# 800U-R3N3_IB_LED_V1_0.net
KiCad netlist of a schematic drawn in Altium Designer
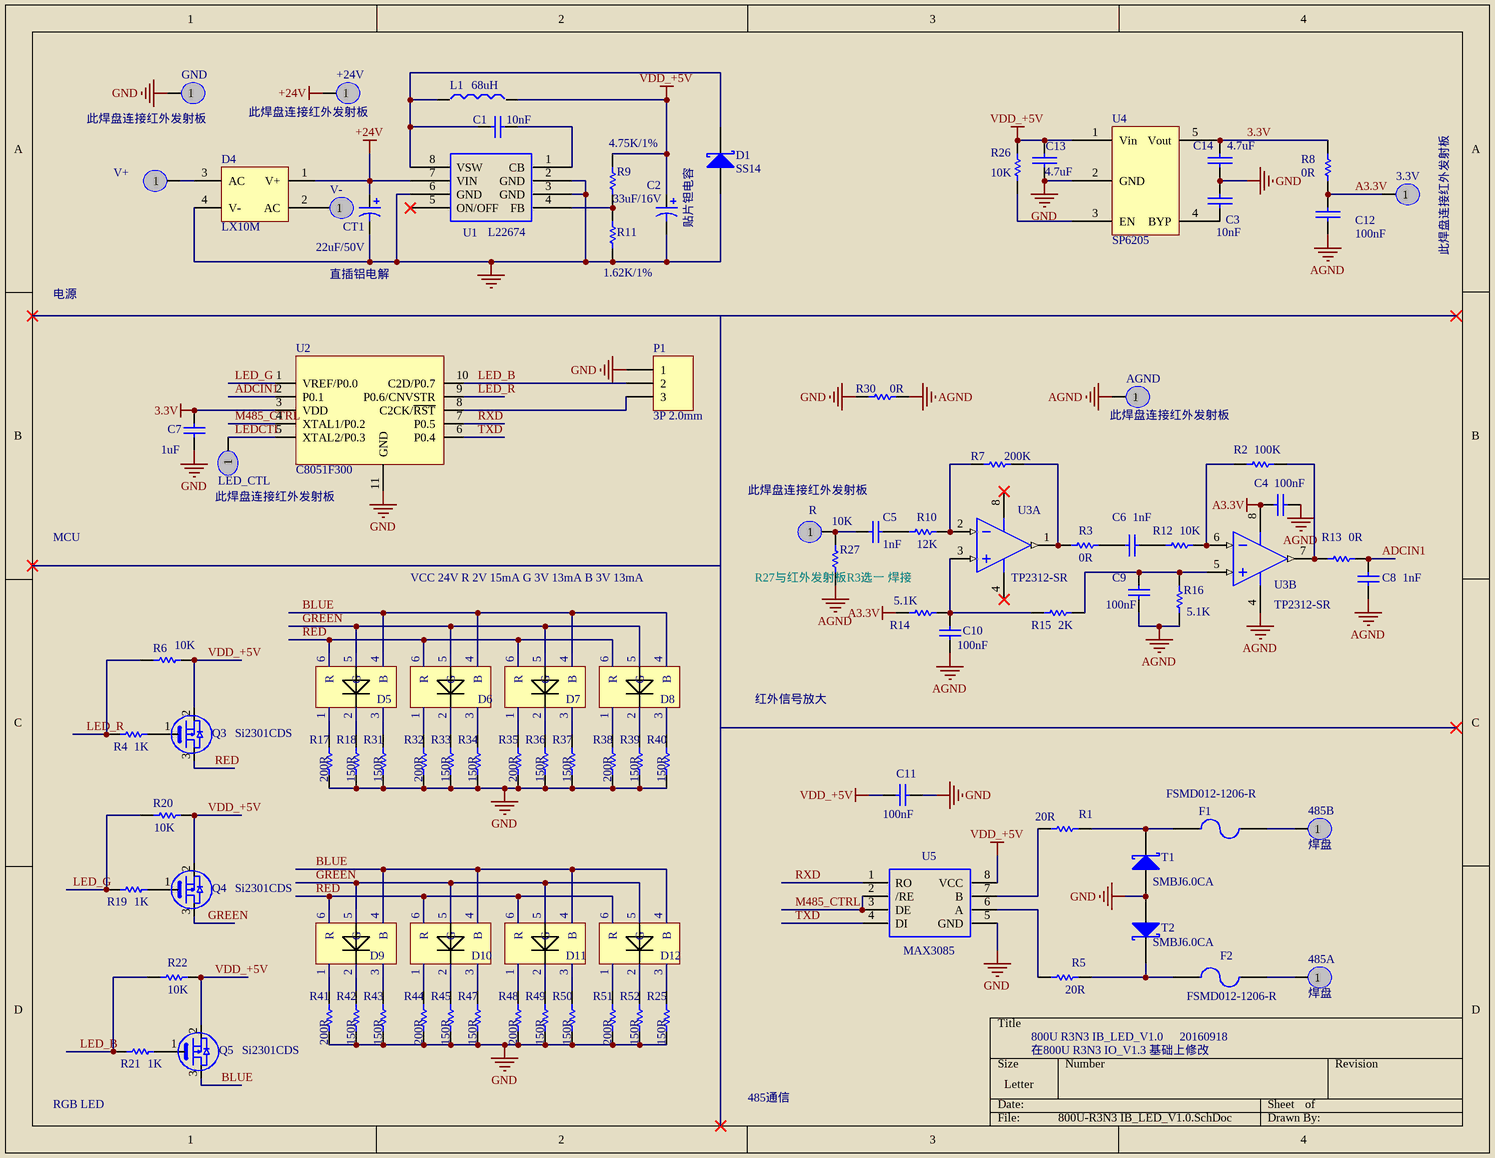
[diagram p0: 800U-R3N3 IB_LED_V1.0.SchDoc]

(export (version "E")
  (design (tool "Eeschema 10.0.6"))
  (components
    (comp (ref "+24V")
      (value "~")
      (footprint "HOLE_SMD")
      (fields (field (name "ALTIUM_UNNAMED_1") "此焊盘连接红外发射板"))
      (libsource (lib "MODBUS_V1.0") (part "焊盘"))
    )
    (comp (ref "3.3V")
      (value "~")
      (footprint "HOLE_SMD")
      (fields (field (name "ALTIUM_UNNAMED_1") "此焊盘连接红外发射板"))
      (libsource (lib "MODBUS_V1.0") (part "焊盘"))
    )
    (comp (ref "485A") (value "焊盘") (footprint "HOLE_SMD") (libsource (lib "MODBUS_V1.0") (part "焊盘")))
    (comp (ref "485B") (value "焊盘") (footprint "HOLE_SMD") (libsource (lib "MODBUS_V1.0") (part "焊盘")))
    (comp (ref "AGND")
      (value "~")
      (footprint "HOLE_SMD")
      (fields (field (name "ALTIUM_UNNAMED_1") "此焊盘连接红外发射板"))
      (libsource (lib "MODBUS_V1.0") (part "焊盘"))
    )
    (comp (ref "C1")
      (value "10nF")
      (footprint "C0603")
      (description "Capacitor")
      (fields (field (name "PUBLISHER") "Altium Limited"))
      (libsource (lib "*") (part "Cap"))
    )
    (comp (ref "C2")
      (value "33uF/16V")
      (footprint "CT3528")
      (description "Polarized Capacitor (Radial)")
      (fields (field (name "KIND") "贴片钽电容"))
      (libsource (lib "*") (part "Cap Pol1"))
    )
    (comp (ref "C3")
      (value "10nF")
      (footprint "C0603")
      (description "Capacitor")
      (libsource (lib "*") (part "CAP"))
    )
    (comp (ref "C4")
      (value "100nF")
      (footprint "C0603")
      (description "Capacitor")
      (fields (field (name "PUBLISHER") "Altium Limited"))
      (libsource (lib "TMJD1.0") (part "Cap"))
    )
    (comp (ref "C5")
      (value "1nF")
      (footprint "C0603")
      (description "Capacitor")
      (fields (field (name "PUBLISHER") "Altium Limited"))
      (libsource (lib "TMJD1.0") (part "Cap"))
    )
    (comp (ref "C6")
      (value "1nF")
      (footprint "C0603")
      (description "Capacitor")
      (fields (field (name "PUBLISHER") "Altium Limited"))
      (libsource (lib "TMJD1.0") (part "Cap"))
    )
    (comp (ref "C7")
      (value "1uF")
      (footprint "C0603")
      (description "贴片电容")
      (fields (field (name "PUBLISHER") "Altium Limited"))
      (libsource (lib "TMJD1.0") (part "Cap"))
    )
    (comp (ref "C8")
      (value "1nF")
      (footprint "C0603")
      (description "Capacitor")
      (fields (field (name "PUBLISHER") "Altium Limited"))
      (libsource (lib "TMJD1.0") (part "Cap"))
    )
    (comp (ref "C9")
      (value "100nF")
      (footprint "C0603")
      (description "Capacitor")
      (fields (field (name "PUBLISHER") "Altium Limited"))
      (libsource (lib "TMJD1.0") (part "Cap"))
    )
    (comp (ref "C10")
      (value "100nF")
      (footprint "C0603")
      (description "Capacitor")
      (fields (field (name "PUBLISHER") "Altium Limited"))
      (libsource (lib "TMJD1.0") (part "Cap"))
    )
    (comp (ref "C11")
      (value "100nF")
      (footprint "C0603")
      (description "贴片陶瓷电容")
      (libsource (lib "Miscellaneous Devices") (part "Cap"))
    )
    (comp (ref "C12")
      (value "100nF")
      (footprint "C0603")
      (description "Capacitor")
      (libsource (lib "*") (part "CAP"))
    )
    (comp (ref "C13")
      (value "4.7uF")
      (footprint "C0603")
      (description "Capacitor")
      (libsource (lib "*") (part "CAP"))
    )
    (comp (ref "C14")
      (value "4.7uF")
      (footprint "C0603")
      (description "Capacitor")
      (libsource (lib "*") (part "CAP"))
    )
    (comp (ref "CT1")
      (value "22uF/50V")
      (footprint "RB0.1")
      (description "Polarized Capacitor (Radial)")
      (fields (field (name "KIND") "直插铝电解"))
      (libsource (lib "*") (part "Cap Pol1"))
    )
    (comp (ref "D1") (value "SS14") (footprint "SMB") (libsource (lib "*") (part "SMBJ6.0CA")))
    (comp (ref "D4")
      (value "LX10M")
      (footprint "桥堆 3.8*3.5")
      (description "贴片桥堆")
      (libsource (lib "Miscellaneous Devices") (part "Bridge2"))
    )
    (comp (ref "D5")
      (value "5050RGB")
      (footprint "5050RGB")
      (description "RBG发光管")
      (libsource (lib "MODBUS_V1.0") (part "5050RGB"))
    )
    (comp (ref "D6")
      (value "5050RGB")
      (footprint "5050RGB")
      (description "RBG发光管")
      (libsource (lib "MODBUS_V1.0") (part "5050RGB"))
    )
    (comp (ref "D7")
      (value "5050RGB")
      (footprint "5050RGB")
      (description "RBG发光管")
      (libsource (lib "MODBUS_V1.0") (part "5050RGB"))
    )
    (comp (ref "D8")
      (value "5050RGB")
      (footprint "5050RGB")
      (description "RBG发光管")
      (libsource (lib "MODBUS_V1.0") (part "5050RGB"))
    )
    (comp (ref "D9")
      (value "5050RGB")
      (footprint "5050RGB")
      (description "RBG发光管")
      (libsource (lib "MODBUS_V1.0") (part "5050RGB"))
    )
    (comp (ref "D10")
      (value "5050RGB")
      (footprint "5050RGB")
      (description "RBG发光管")
      (libsource (lib "MODBUS_V1.0") (part "5050RGB"))
    )
    (comp (ref "D11")
      (value "5050RGB")
      (footprint "5050RGB")
      (description "RBG发光管")
      (libsource (lib "MODBUS_V1.0") (part "5050RGB"))
    )
    (comp (ref "D12")
      (value "5050RGB")
      (footprint "5050RGB")
      (description "RBG发光管")
      (libsource (lib "MODBUS_V1.0") (part "5050RGB"))
    )
    (comp (ref "F1")
      (value "FSMD012-1206-R")
      (footprint "1206")
      (description "可恢复保险丝")
      (libsource (lib "Miscellaneous Devices") (part "Fuse 2"))
    )
    (comp (ref "F2")
      (value "FSMD012-1206-R")
      (footprint "1206")
      (description "可恢复保险丝")
      (libsource (lib "Miscellaneous Devices") (part "Fuse 2"))
    )
    (comp (ref "GND")
      (value "~")
      (footprint "HOLE_SMD")
      (fields (field (name "ALTIUM_UNNAMED_1") "此焊盘连接红外发射板"))
      (libsource (lib "MODBUS_V1.0") (part "焊盘"))
    )
    (comp (ref "L1") (value "68uH") (footprint "L-6X6") (libsource (lib "*") (part "电感")))
    (comp (ref "LED_CTL")
      (value "~")
      (footprint "HOLE_SMD")
      (fields (field (name "ALTIUM_UNNAMED_1") "此焊盘连接红外发射板"))
      (libsource (lib "MODBUS_V1.0") (part "焊盘"))
    )
    (comp (ref "P1")
      (value "3P 2.0mm")
      (footprint "SIP3")
      (description "插座")
      (fields (field (name "PUBLISHER") "Altium Limited"))
      (libsource (lib "Miscellaneous Connectors") (part "MHDR1X3"))
    )
    (comp (ref "Q3")
      (value "Si2301CDS")
      (footprint "SOT-23")
      (description "贴片MOS管")
      (libsource (lib "BATTERY") (part "P-MOSFET"))
    )
    (comp (ref "Q4")
      (value "Si2301CDS")
      (footprint "SOT-23")
      (description "贴片MOS管")
      (libsource (lib "BATTERY") (part "P-MOSFET"))
    )
    (comp (ref "Q5")
      (value "Si2301CDS")
      (footprint "SOT-23")
      (description "贴片MOS管")
      (libsource (lib "BATTERY") (part "P-MOSFET"))
    )
    (comp (ref "R")
      (value "~")
      (footprint "HOLE_SMD")
      (fields (field (name "ALTIUM_UNNAMED_1") "此焊盘连接红外发射板"))
      (libsource (lib "MODBUS_V1.0") (part "焊盘"))
    )
    (comp (ref "R1")
      (value "20R")
      (footprint "2010")
      (description "贴片电阻")
      (libsource (lib "Miscellaneous Devices") (part "Res Semi"))
    )
    (comp (ref "R2")
      (value "100K")
      (footprint "R0603")
      (description "Semiconductor Resistor")
      (libsource (lib "Miscellaneous Devices") (part "Res Semi"))
    )
    (comp (ref "R3")
      (value "0R")
      (footprint "R0603")
      (description "Semiconductor Resistor")
      (libsource (lib "Miscellaneous Devices") (part "Res Semi"))
    )
    (comp (ref "R4")
      (value "1K")
      (footprint "R0603")
      (description "贴片电阻")
      (libsource (lib "Miscellaneous Devices") (part "Res Semi"))
    )
    (comp (ref "R5")
      (value "20R")
      (footprint "2010")
      (description "贴片电阻")
      (libsource (lib "Miscellaneous Devices") (part "Res Semi"))
    )
    (comp (ref "R6")
      (value "10K")
      (footprint "R0603")
      (description "贴片电阻")
      (libsource (lib "Miscellaneous Devices") (part "Res Semi"))
    )
    (comp (ref "R7")
      (value "200K")
      (footprint "R0603")
      (description "Semiconductor Resistor")
      (libsource (lib "Miscellaneous Devices") (part "Res Semi"))
    )
    (comp (ref "R8")
      (value "0R")
      (footprint "R0603")
      (description "Resistor")
      (fields (field (name "PUBLISHER") "Altium Limited"))
      (libsource (lib "*") (part "Res1"))
    )
    (comp (ref "R9")
      (value "4.75K/1%")
      (footprint "R0603")
      (description "Semiconductor Resistor")
      (fields (field (name "PUBLISHER") "Altium Limited"))
      (libsource (lib "*") (part "Res Semi"))
    )
    (comp (ref "R10")
      (value "12K")
      (footprint "R0603")
      (description "Semiconductor Resistor")
      (libsource (lib "Miscellaneous Devices") (part "Res Semi"))
    )
    (comp (ref "R11")
      (value "1.62K/1%")
      (footprint "R0603")
      (description "Semiconductor Resistor")
      (fields (field (name "PUBLISHER") "Altium Limited"))
      (libsource (lib "*") (part "Res Semi"))
    )
    (comp (ref "R12")
      (value "10K")
      (footprint "R0603")
      (description "Semiconductor Resistor")
      (libsource (lib "Miscellaneous Devices") (part "Res Semi"))
    )
    (comp (ref "R13")
      (value "0R")
      (footprint "R0603")
      (description "Semiconductor Resistor")
      (libsource (lib "Miscellaneous Devices") (part "Res Semi"))
    )
    (comp (ref "R14")
      (value "5.1K")
      (footprint "R0603")
      (description "Semiconductor Resistor")
      (libsource (lib "Miscellaneous Devices") (part "Res Semi"))
    )
    (comp (ref "R15")
      (value "2K")
      (footprint "R0603")
      (description "Semiconductor Resistor")
      (libsource (lib "Miscellaneous Devices") (part "Res Semi"))
    )
    (comp (ref "R16")
      (value "5.1K")
      (footprint "R0603")
      (description "Semiconductor Resistor")
      (libsource (lib "Miscellaneous Devices") (part "Res Semi"))
    )
    (comp (ref "R17")
      (value "200R")
      (footprint "0805")
      (description "贴片电阻")
      (libsource (lib "Miscellaneous Devices") (part "Res Semi"))
    )
    (comp (ref "R18")
      (value "150R")
      (footprint "0805")
      (description "贴片电阻")
      (libsource (lib "Miscellaneous Devices") (part "Res Semi"))
    )
    (comp (ref "R19")
      (value "1K")
      (footprint "R0603")
      (description "贴片电阻")
      (libsource (lib "Miscellaneous Devices") (part "Res Semi"))
    )
    (comp (ref "R20")
      (value "10K")
      (footprint "R0603")
      (description "贴片电阻")
      (libsource (lib "Miscellaneous Devices") (part "Res Semi"))
    )
    (comp (ref "R21")
      (value "1K")
      (footprint "R0603")
      (description "贴片电阻")
      (libsource (lib "Miscellaneous Devices") (part "Res Semi"))
    )
    (comp (ref "R22")
      (value "10K")
      (footprint "R0603")
      (description "贴片电阻")
      (libsource (lib "Miscellaneous Devices") (part "Res Semi"))
    )
    (comp (ref "R25")
      (value "150R")
      (footprint "0805")
      (description "贴片电阻")
      (libsource (lib "Miscellaneous Devices") (part "Res Semi"))
    )
    (comp (ref "R26")
      (value "10K")
      (footprint "R0603")
      (description "Resistor")
      (fields (field (name "PUBLISHER") "Altium Limited"))
      (libsource (lib "*") (part "Res1"))
    )
    (comp (ref "R27")
      (value "10K")
      (footprint "R0603")
      (description "Semiconductor Resistor")
      (fields (field (name "ALTIUM_UNNAMED_1") "R27与红外发射板R3选一 焊接"))
      (libsource (lib "Miscellaneous Devices") (part "Res Semi"))
    )
    (comp (ref "R30")
      (value "0R")
      (footprint "R0603")
      (description "Semiconductor Resistor")
      (libsource (lib "Miscellaneous Devices") (part "Res Semi"))
    )
    (comp (ref "R31")
      (value "150R")
      (footprint "0805")
      (description "贴片电阻")
      (libsource (lib "Miscellaneous Devices") (part "Res Semi"))
    )
    (comp (ref "R32")
      (value "200R")
      (footprint "0805")
      (description "贴片电阻")
      (libsource (lib "Miscellaneous Devices") (part "Res Semi"))
    )
    (comp (ref "R33")
      (value "150R")
      (footprint "0805")
      (description "贴片电阻")
      (libsource (lib "Miscellaneous Devices") (part "Res Semi"))
    )
    (comp (ref "R34")
      (value "150R")
      (footprint "0805")
      (description "贴片电阻")
      (libsource (lib "Miscellaneous Devices") (part "Res Semi"))
    )
    (comp (ref "R35")
      (value "200R")
      (footprint "0805")
      (description "贴片电阻")
      (libsource (lib "Miscellaneous Devices") (part "Res Semi"))
    )
    (comp (ref "R36")
      (value "150R")
      (footprint "0805")
      (description "贴片电阻")
      (libsource (lib "Miscellaneous Devices") (part "Res Semi"))
    )
    (comp (ref "R37")
      (value "150R")
      (footprint "0805")
      (description "贴片电阻")
      (libsource (lib "Miscellaneous Devices") (part "Res Semi"))
    )
    (comp (ref "R38")
      (value "200R")
      (footprint "0805")
      (description "贴片电阻")
      (libsource (lib "Miscellaneous Devices") (part "Res Semi"))
    )
    (comp (ref "R39")
      (value "150R")
      (footprint "0805")
      (description "贴片电阻")
      (libsource (lib "Miscellaneous Devices") (part "Res Semi"))
    )
    (comp (ref "R40")
      (value "150R")
      (footprint "0805")
      (description "贴片电阻")
      (libsource (lib "Miscellaneous Devices") (part "Res Semi"))
    )
    (comp (ref "R41")
      (value "200R")
      (footprint "0805")
      (description "贴片电阻")
      (libsource (lib "Miscellaneous Devices") (part "Res Semi"))
    )
    (comp (ref "R42")
      (value "150R")
      (footprint "0805")
      (description "贴片电阻")
      (libsource (lib "Miscellaneous Devices") (part "Res Semi"))
    )
    (comp (ref "R43")
      (value "150R")
      (footprint "0805")
      (description "贴片电阻")
      (libsource (lib "Miscellaneous Devices") (part "Res Semi"))
    )
    (comp (ref "R44")
      (value "200R")
      (footprint "0805")
      (description "贴片电阻")
      (libsource (lib "Miscellaneous Devices") (part "Res Semi"))
    )
    (comp (ref "R45")
      (value "150R")
      (footprint "0805")
      (description "贴片电阻")
      (libsource (lib "Miscellaneous Devices") (part "Res Semi"))
    )
    (comp (ref "R47")
      (value "150R")
      (footprint "0805")
      (description "贴片电阻")
      (libsource (lib "Miscellaneous Devices") (part "Res Semi"))
    )
    (comp (ref "R48")
      (value "200R")
      (footprint "0805")
      (description "贴片电阻")
      (libsource (lib "Miscellaneous Devices") (part "Res Semi"))
    )
    (comp (ref "R49")
      (value "150R")
      (footprint "0805")
      (description "贴片电阻")
      (libsource (lib "Miscellaneous Devices") (part "Res Semi"))
    )
    (comp (ref "R50")
      (value "150R")
      (footprint "0805")
      (description "贴片电阻")
      (libsource (lib "Miscellaneous Devices") (part "Res Semi"))
    )
    (comp (ref "R51")
      (value "200R")
      (footprint "0805")
      (description "贴片电阻")
      (libsource (lib "Miscellaneous Devices") (part "Res Semi"))
    )
    (comp (ref "R52")
      (value "150R")
      (footprint "0805")
      (description "贴片电阻")
      (libsource (lib "Miscellaneous Devices") (part "Res Semi"))
    )
    (comp (ref "T1")
      (value "~")
      (footprint "HSMA")
      (description "TVS管")
      (fields (field (name "型号") "SMBJ6.0CA"))
      (libsource (lib "MODBUS_V1.0") (part "SMBJ6.0CA"))
    )
    (comp (ref "T2")
      (value "~")
      (footprint "HSMA")
      (description "TVS管")
      (fields (field (name "型号") "SMBJ6.0CA"))
      (libsource (lib "MODBUS_V1.0") (part "SMBJ6.0CA"))
    )
    (comp (ref "U1") (value "L22674") (footprint "SO-1.27-9/4.0") (libsource (lib "*") (part "2674")))
    (comp (ref "U2")
      (value "C8051F300")
      (footprint "QFN-11")
      (description "贴片芯片")
      (libsource (lib "集成块") (part "PIC16C505"))
    )
    (comp (ref "U3")
      (value "TP2312-SR")
      (footprint "SO-8")
      (description "Dual Low Noise, Audio Amplifier")
      (fields (field (name "PUBLISHER") "Altium Limited"))
      (libsource (lib "Motorola Amplifier Audio Amplifier") (part "LM833D"))
    )
    (comp (ref "U4")
      (value "SP6205")
      (footprint "SOT-23-5")
      (libsource (lib "MODBUS_V1.0") (part "SP6203/SP6205"))
    )
    (comp (ref "U5")
      (value "MAX3085")
      (footprint "SO-1.27-8/4.0")
      (description "贴片芯片")
      (libsource (lib "*") (part "MAX_485"))
    )
    (comp (ref "V+") (value "~") (footprint "HOLE_SMD") (libsource (lib "MODBUS_V1.0") (part "焊盘")))
    (comp (ref "V-") (value "~") (footprint "HOLE_SMD") (libsource (lib "MODBUS_V1.0") (part "焊盘")))
  )
  (nets
    (net (code "1") (name "+24V") (class "Default")
      (node (ref "+24V") (pin "1") (pinfunction "1_1") (pintype "passive"))
      (node (ref "CT1") (pin "1") (pinfunction "1_1") (pintype "passive"))
      (node (ref "D4") (pin "1") (pinfunction "V+_1") (pintype "passive"))
      (node (ref "U1") (pin "7") (pinfunction "VIN_7") (pintype "passive"))
    )
    (net (code "2") (name "/ADCIN1") (class "Default")
      (node (ref "C8") (pin "2") (pinfunction "2_2") (pintype "passive"))
      (node (ref "R13") (pin "2") (pinfunction "2_2") (pintype "passive"))
      (node (ref "U2") (pin "2") (pinfunction "P0.1_2") (pintype "passive"))
    )
    (net (code "3") (name "/BLUE") (class "Default")
      (node (ref "D10") (pin "4") (pinfunction "B_4") (pintype "passive"))
      (node (ref "D11") (pin "4") (pinfunction "B_4") (pintype "passive"))
      (node (ref "D12") (pin "4") (pinfunction "B_4") (pintype "passive"))
      (node (ref "D5") (pin "4") (pinfunction "B_4") (pintype "passive"))
      (node (ref "D6") (pin "4") (pinfunction "B_4") (pintype "passive"))
      (node (ref "D7") (pin "4") (pinfunction "B_4") (pintype "passive"))
      (node (ref "D8") (pin "4") (pinfunction "B_4") (pintype "passive"))
      (node (ref "D9") (pin "4") (pinfunction "B_4") (pintype "passive"))
      (node (ref "Q5") (pin "3") (pinfunction "D_3") (pintype "passive"))
    )
    (net (code "4") (name "/GREEN") (class "Default")
      (node (ref "D10") (pin "5") (pinfunction "G_5") (pintype "passive"))
      (node (ref "D11") (pin "5") (pinfunction "G_5") (pintype "passive"))
      (node (ref "D12") (pin "5") (pinfunction "G_5") (pintype "passive"))
      (node (ref "D5") (pin "5") (pinfunction "G_5") (pintype "passive"))
      (node (ref "D6") (pin "5") (pinfunction "G_5") (pintype "passive"))
      (node (ref "D7") (pin "5") (pinfunction "G_5") (pintype "passive"))
      (node (ref "D8") (pin "5") (pinfunction "G_5") (pintype "passive"))
      (node (ref "D9") (pin "5") (pinfunction "G_5") (pintype "passive"))
      (node (ref "Q4") (pin "3") (pinfunction "D_3") (pintype "passive"))
    )
    (net (code "5") (name "/LEDCTL") (class "Default")
      (node (ref "LED_CTL") (pin "1") (pinfunction "1_1") (pintype "passive"))
      (node (ref "U2") (pin "5") (pinfunction "XTAL2/P0.3_5") (pintype "passive"))
    )
    (net (code "6") (name "/LED_B") (class "Default")
      (node (ref "P1") (pin "2") (pinfunction "2_2") (pintype "passive"))
      (node (ref "R21") (pin "2") (pinfunction "2_2") (pintype "passive"))
      (node (ref "R22") (pin "2") (pinfunction "2_2") (pintype "passive"))
      (node (ref "U2") (pin "10") (pinfunction "C2D/P0.7_10") (pintype "passive"))
    )
    (net (code "7") (name "/LED_G") (class "Default")
      (node (ref "R19") (pin "2") (pinfunction "2_2") (pintype "passive"))
      (node (ref "R20") (pin "2") (pinfunction "2_2") (pintype "passive"))
      (node (ref "U2") (pin "1") (pinfunction "VREF/P0.0_1") (pintype "passive"))
    )
    (net (code "8") (name "/LED_R") (class "Default")
      (node (ref "R4") (pin "2") (pinfunction "2_2") (pintype "passive"))
      (node (ref "R6") (pin "2") (pinfunction "2_2") (pintype "passive"))
      (node (ref "U2") (pin "9") (pinfunction "P0.6/CNVSTR_9") (pintype "passive"))
    )
    (net (code "9") (name "/M485_CTRL") (class "Default")
      (node (ref "U2") (pin "4") (pinfunction "XTAL1/P0.2_4") (pintype "passive"))
      (node (ref "U5") (pin "2") (pinfunction "/RE_2") (pintype "passive"))
      (node (ref "U5") (pin "3") (pinfunction "DE_3") (pintype "passive"))
    )
    (net (code "10") (name "/RED") (class "Default")
      (node (ref "D10") (pin "6") (pinfunction "R_6") (pintype "passive"))
      (node (ref "D11") (pin "6") (pinfunction "R_6") (pintype "passive"))
      (node (ref "D12") (pin "6") (pinfunction "R_6") (pintype "passive"))
      (node (ref "D5") (pin "6") (pinfunction "R_6") (pintype "passive"))
      (node (ref "D6") (pin "6") (pinfunction "R_6") (pintype "passive"))
      (node (ref "D7") (pin "6") (pinfunction "R_6") (pintype "passive"))
      (node (ref "D8") (pin "6") (pinfunction "R_6") (pintype "passive"))
      (node (ref "D9") (pin "6") (pinfunction "R_6") (pintype "passive"))
      (node (ref "Q3") (pin "3") (pinfunction "D_3") (pintype "passive"))
    )
    (net (code "11") (name "/RXD") (class "Default")
      (node (ref "U2") (pin "7") (pinfunction "P0.5_7") (pintype "passive"))
      (node (ref "U5") (pin "1") (pinfunction "RO_1") (pintype "passive"))
    )
    (net (code "12") (name "/TXD") (class "Default")
      (node (ref "U2") (pin "6") (pinfunction "P0.4_6") (pintype "passive"))
      (node (ref "U5") (pin "4") (pinfunction "DI_4") (pintype "passive"))
    )
    (net (code "13") (name "3.3V") (class "Default")
      (node (ref "C14") (pin "1") (pinfunction "1_1") (pintype "passive"))
      (node (ref "C7") (pin "1") (pinfunction "1_1") (pintype "passive"))
      (node (ref "R8") (pin "1") (pinfunction "1_1") (pintype "passive"))
      (node (ref "U2") (pin "3") (pinfunction "VDD_3") (pintype "passive"))
      (node (ref "U4") (pin "5") (pinfunction "Vout_5") (pintype "passive"))
    )
    (net (code "14") (name "A3.3V") (class "Default")
      (node (ref "3.3V") (pin "1") (pinfunction "1_1") (pintype "passive"))
      (node (ref "C12") (pin "2") (pinfunction "2_2") (pintype "passive"))
      (node (ref "C4") (pin "1") (pinfunction "1_1") (pintype "passive"))
      (node (ref "R14") (pin "1") (pinfunction "1_1") (pintype "passive"))
      (node (ref "R8") (pin "2") (pinfunction "2_2") (pintype "passive"))
      (node (ref "U3") (pin "8") (pinfunction "VCC_8") (pintype "power_in"))
    )
    (net (code "15") (name "AGND") (class "Default")
      (node (ref "AGND") (pin "1") (pinfunction "1_1") (pintype "passive"))
      (node (ref "C10") (pin "2") (pinfunction "2_2") (pintype "passive"))
      (node (ref "C12") (pin "1") (pinfunction "1_1") (pintype "passive"))
      (node (ref "C4") (pin "2") (pinfunction "2_2") (pintype "passive"))
      (node (ref "C8") (pin "1") (pinfunction "1_1") (pintype "passive"))
      (node (ref "C9") (pin "2") (pinfunction "2_2") (pintype "passive"))
      (node (ref "R16") (pin "1") (pinfunction "1_1") (pintype "passive"))
      (node (ref "R27") (pin "2") (pinfunction "2_2") (pintype "passive"))
      (node (ref "R30") (pin "2") (pinfunction "2_2") (pintype "passive"))
      (node (ref "U3") (pin "4") (pinfunction "VEE_4") (pintype "power_in"))
    )
    (net (code "16") (name "GND") (class "Default")
      (node (ref "C11") (pin "1") (pinfunction "1_1") (pintype "passive"))
      (node (ref "C13") (pin "2") (pinfunction "2_2") (pintype "passive"))
      (node (ref "C14") (pin "2") (pinfunction "2_2") (pintype "passive"))
      (node (ref "C2") (pin "2") (pinfunction "2_2") (pintype "passive"))
      (node (ref "C3") (pin "2") (pinfunction "2_2") (pintype "passive"))
      (node (ref "C7") (pin "2") (pinfunction "2_2") (pintype "passive"))
      (node (ref "CT1") (pin "2") (pinfunction "2_2") (pintype "passive"))
      (node (ref "D1") (pin "1") (pinfunction "A_1") (pintype "passive"))
      (node (ref "D4") (pin "4") (pinfunction "V-_4") (pintype "passive"))
      (node (ref "GND") (pin "1") (pinfunction "1_1") (pintype "passive"))
      (node (ref "P1") (pin "1") (pinfunction "1_1") (pintype "passive"))
      (node (ref "R11") (pin "1") (pinfunction "1_1") (pintype "passive"))
      (node (ref "R17") (pin "1") (pinfunction "1_1") (pintype "passive"))
      (node (ref "R18") (pin "1") (pinfunction "1_1") (pintype "passive"))
      (node (ref "R25") (pin "1") (pinfunction "1_1") (pintype "passive"))
      (node (ref "R30") (pin "1") (pinfunction "1_1") (pintype "passive"))
      (node (ref "R31") (pin "1") (pinfunction "1_1") (pintype "passive"))
      (node (ref "R32") (pin "1") (pinfunction "1_1") (pintype "passive"))
      (node (ref "R33") (pin "1") (pinfunction "1_1") (pintype "passive"))
      (node (ref "R34") (pin "1") (pinfunction "1_1") (pintype "passive"))
      (node (ref "R35") (pin "1") (pinfunction "1_1") (pintype "passive"))
      (node (ref "R36") (pin "1") (pinfunction "1_1") (pintype "passive"))
      (node (ref "R37") (pin "1") (pinfunction "1_1") (pintype "passive"))
      (node (ref "R38") (pin "1") (pinfunction "1_1") (pintype "passive"))
      (node (ref "R39") (pin "1") (pinfunction "1_1") (pintype "passive"))
      (node (ref "R40") (pin "1") (pinfunction "1_1") (pintype "passive"))
      (node (ref "R41") (pin "1") (pinfunction "1_1") (pintype "passive"))
      (node (ref "R42") (pin "1") (pinfunction "1_1") (pintype "passive"))
      (node (ref "R43") (pin "1") (pinfunction "1_1") (pintype "passive"))
      (node (ref "R44") (pin "1") (pinfunction "1_1") (pintype "passive"))
      (node (ref "R45") (pin "1") (pinfunction "1_1") (pintype "passive"))
      (node (ref "R47") (pin "1") (pinfunction "1_1") (pintype "passive"))
      (node (ref "R48") (pin "1") (pinfunction "1_1") (pintype "passive"))
      (node (ref "R49") (pin "1") (pinfunction "1_1") (pintype "passive"))
      (node (ref "R50") (pin "1") (pinfunction "1_1") (pintype "passive"))
      (node (ref "R51") (pin "1") (pinfunction "1_1") (pintype "passive"))
      (node (ref "R52") (pin "1") (pinfunction "1_1") (pintype "passive"))
      (node (ref "T1") (pin "1") (pinfunction "A_1") (pintype "passive"))
      (node (ref "T2") (pin "1") (pinfunction "A_1") (pintype "passive"))
      (node (ref "U1") (pin "2") (pinfunction "GND_2") (pintype "passive"))
      (node (ref "U1") (pin "3") (pinfunction "GND_3") (pintype "passive"))
      (node (ref "U1") (pin "6") (pinfunction "GND_6") (pintype "passive"))
      (node (ref "U2") (pin "11") (pinfunction "GND_11") (pintype "passive"))
      (node (ref "U4") (pin "2") (pinfunction "GND_2") (pintype "passive"))
      (node (ref "U5") (pin "5") (pinfunction "GND_5") (pintype "passive"))
    )
    (net (code "17") (name "Net-(485A-Pad1)") (class "Default")
      (node (ref "485A") (pin "1") (pinfunction "1_1") (pintype "passive"))
      (node (ref "F2") (pin "2") (pinfunction "2_2") (pintype "passive"))
    )
    (net (code "18") (name "Net-(485B-Pad1)") (class "Default")
      (node (ref "485B") (pin "1") (pinfunction "1_1") (pintype "passive"))
      (node (ref "F1") (pin "2") (pinfunction "2_2") (pintype "passive"))
    )
    (net (code "19") (name "Net-(C5-Pad1)") (class "Default")
      (node (ref "C5") (pin "1") (pinfunction "1_1") (pintype "passive"))
      (node (ref "R") (pin "1") (pinfunction "1_1") (pintype "passive"))
      (node (ref "R27") (pin "1") (pinfunction "1_1") (pintype "passive"))
    )
    (net (code "20") (name "Net-(C5-Pad2)") (class "Default")
      (node (ref "C5") (pin "2") (pinfunction "2_2") (pintype "passive"))
      (node (ref "R10") (pin "1") (pinfunction "1_1") (pintype "passive"))
    )
    (net (code "21") (name "Net-(C6-Pad1)") (class "Default")
      (node (ref "C6") (pin "1") (pinfunction "1_1") (pintype "passive"))
      (node (ref "R3") (pin "2") (pinfunction "2_2") (pintype "passive"))
    )
    (net (code "22") (name "Net-(C6-Pad2)") (class "Default")
      (node (ref "C6") (pin "2") (pinfunction "2_2") (pintype "passive"))
      (node (ref "R12") (pin "1") (pinfunction "1_1") (pintype "passive"))
    )
    (net (code "23") (name "Net-(D1-K)") (class "Default")
      (node (ref "C1") (pin "2") (pinfunction "2_2") (pintype "passive"))
      (node (ref "D1") (pin "2") (pinfunction "K_2") (pintype "passive"))
      (node (ref "L1") (pin "1") (pinfunction "1_1") (pintype "passive"))
      (node (ref "U1") (pin "8") (pinfunction "VSW_8") (pintype "passive"))
    )
    (net (code "24") (name "Net-(D4-AC-Pad2)") (class "Default")
      (node (ref "D4") (pin "2") (pinfunction "AC_2") (pintype "passive"))
      (node (ref "V-") (pin "1") (pinfunction "1_1") (pintype "passive"))
    )
    (net (code "25") (name "Net-(D4-AC-Pad3)") (class "Default")
      (node (ref "D4") (pin "3") (pinfunction "AC_3") (pintype "passive"))
      (node (ref "V+") (pin "1") (pinfunction "1_1") (pintype "passive"))
    )
    (net (code "26") (name "Net-(D5-Pad1)") (class "Default")
      (node (ref "D5") (pin "1") (pintype "passive"))
      (node (ref "R17") (pin "2") (pinfunction "2_2") (pintype "passive"))
    )
    (net (code "27") (name "Net-(D5-Pad2)") (class "Default")
      (node (ref "D5") (pin "2") (pintype "passive"))
      (node (ref "R18") (pin "2") (pinfunction "2_2") (pintype "passive"))
    )
    (net (code "28") (name "Net-(D5-Pad3)") (class "Default")
      (node (ref "D5") (pin "3") (pintype "passive"))
      (node (ref "R31") (pin "2") (pinfunction "2_2") (pintype "passive"))
    )
    (net (code "29") (name "Net-(D6-Pad1)") (class "Default")
      (node (ref "D6") (pin "1") (pintype "passive"))
      (node (ref "R32") (pin "2") (pinfunction "2_2") (pintype "passive"))
    )
    (net (code "30") (name "Net-(D6-Pad2)") (class "Default")
      (node (ref "D6") (pin "2") (pintype "passive"))
      (node (ref "R33") (pin "2") (pinfunction "2_2") (pintype "passive"))
    )
    (net (code "31") (name "Net-(D6-Pad3)") (class "Default")
      (node (ref "D6") (pin "3") (pintype "passive"))
      (node (ref "R34") (pin "2") (pinfunction "2_2") (pintype "passive"))
    )
    (net (code "32") (name "Net-(D7-Pad1)") (class "Default")
      (node (ref "D7") (pin "1") (pintype "passive"))
      (node (ref "R35") (pin "2") (pinfunction "2_2") (pintype "passive"))
    )
    (net (code "33") (name "Net-(D7-Pad2)") (class "Default")
      (node (ref "D7") (pin "2") (pintype "passive"))
      (node (ref "R36") (pin "2") (pinfunction "2_2") (pintype "passive"))
    )
    (net (code "34") (name "Net-(D7-Pad3)") (class "Default")
      (node (ref "D7") (pin "3") (pintype "passive"))
      (node (ref "R37") (pin "2") (pinfunction "2_2") (pintype "passive"))
    )
    (net (code "35") (name "Net-(D8-Pad1)") (class "Default")
      (node (ref "D8") (pin "1") (pintype "passive"))
      (node (ref "R38") (pin "2") (pinfunction "2_2") (pintype "passive"))
    )
    (net (code "36") (name "Net-(D8-Pad2)") (class "Default")
      (node (ref "D8") (pin "2") (pintype "passive"))
      (node (ref "R39") (pin "2") (pinfunction "2_2") (pintype "passive"))
    )
    (net (code "37") (name "Net-(D8-Pad3)") (class "Default")
      (node (ref "D8") (pin "3") (pintype "passive"))
      (node (ref "R40") (pin "2") (pinfunction "2_2") (pintype "passive"))
    )
    (net (code "38") (name "Net-(D9-Pad1)") (class "Default")
      (node (ref "D9") (pin "1") (pintype "passive"))
      (node (ref "R41") (pin "2") (pinfunction "2_2") (pintype "passive"))
    )
    (net (code "39") (name "Net-(D9-Pad2)") (class "Default")
      (node (ref "D9") (pin "2") (pintype "passive"))
      (node (ref "R42") (pin "2") (pinfunction "2_2") (pintype "passive"))
    )
    (net (code "40") (name "Net-(D9-Pad3)") (class "Default")
      (node (ref "D9") (pin "3") (pintype "passive"))
      (node (ref "R43") (pin "2") (pinfunction "2_2") (pintype "passive"))
    )
    (net (code "41") (name "Net-(D10-Pad1)") (class "Default")
      (node (ref "D10") (pin "1") (pintype "passive"))
      (node (ref "R44") (pin "2") (pinfunction "2_2") (pintype "passive"))
    )
    (net (code "42") (name "Net-(D10-Pad2)") (class "Default")
      (node (ref "D10") (pin "2") (pintype "passive"))
      (node (ref "R45") (pin "2") (pinfunction "2_2") (pintype "passive"))
    )
    (net (code "43") (name "Net-(D10-Pad3)") (class "Default")
      (node (ref "D10") (pin "3") (pintype "passive"))
      (node (ref "R47") (pin "2") (pinfunction "2_2") (pintype "passive"))
    )
    (net (code "44") (name "Net-(D11-Pad1)") (class "Default")
      (node (ref "D11") (pin "1") (pintype "passive"))
      (node (ref "R48") (pin "2") (pinfunction "2_2") (pintype "passive"))
    )
    (net (code "45") (name "Net-(D11-Pad2)") (class "Default")
      (node (ref "D11") (pin "2") (pintype "passive"))
      (node (ref "R49") (pin "2") (pinfunction "2_2") (pintype "passive"))
    )
    (net (code "46") (name "Net-(D11-Pad3)") (class "Default")
      (node (ref "D11") (pin "3") (pintype "passive"))
      (node (ref "R50") (pin "2") (pinfunction "2_2") (pintype "passive"))
    )
    (net (code "47") (name "Net-(D12-Pad1)") (class "Default")
      (node (ref "D12") (pin "1") (pintype "passive"))
      (node (ref "R51") (pin "2") (pinfunction "2_2") (pintype "passive"))
    )
    (net (code "48") (name "Net-(D12-Pad2)") (class "Default")
      (node (ref "D12") (pin "2") (pintype "passive"))
      (node (ref "R52") (pin "2") (pinfunction "2_2") (pintype "passive"))
    )
    (net (code "49") (name "Net-(D12-Pad3)") (class "Default")
      (node (ref "D12") (pin "3") (pintype "passive"))
      (node (ref "R25") (pin "2") (pinfunction "2_2") (pintype "passive"))
    )
    (net (code "50") (name "Net-(Q3-G)") (class "Default")
      (node (ref "Q3") (pin "1") (pinfunction "G_1") (pintype "passive"))
      (node (ref "R4") (pin "1") (pinfunction "1_1") (pintype "passive"))
    )
    (net (code "51") (name "Net-(Q4-G)") (class "Default")
      (node (ref "Q4") (pin "1") (pinfunction "G_1") (pintype "passive"))
      (node (ref "R19") (pin "1") (pinfunction "1_1") (pintype "passive"))
    )
    (net (code "52") (name "Net-(Q5-G)") (class "Default")
      (node (ref "Q5") (pin "1") (pinfunction "G_1") (pintype "passive"))
      (node (ref "R21") (pin "1") (pinfunction "1_1") (pintype "passive"))
    )
    (net (code "53") (name "Net-(T1-K)") (class "Default")
      (node (ref "F1") (pin "1") (pinfunction "1_1") (pintype "passive"))
      (node (ref "R1") (pin "1") (pinfunction "1_1") (pintype "passive"))
      (node (ref "T1") (pin "2") (pinfunction "K_2") (pintype "passive"))
    )
    (net (code "54") (name "Net-(T2-K)") (class "Default")
      (node (ref "F2") (pin "1") (pinfunction "1_1") (pintype "passive"))
      (node (ref "R5") (pin "1") (pinfunction "1_1") (pintype "passive"))
      (node (ref "T2") (pin "2") (pinfunction "K_2") (pintype "passive"))
    )
    (net (code "55") (name "Net-(U1-CB)") (class "Default")
      (node (ref "C1") (pin "1") (pinfunction "1_1") (pintype "passive"))
      (node (ref "U1") (pin "1") (pinfunction "CB_1") (pintype "passive"))
    )
    (net (code "56") (name "Net-(U1-FB)") (class "Default")
      (node (ref "R11") (pin "2") (pinfunction "2_2") (pintype "passive"))
      (node (ref "R9") (pin "1") (pinfunction "1_1") (pintype "passive"))
      (node (ref "U1") (pin "4") (pinfunction "FB_4") (pintype "passive"))
    )
    (net (code "57") (name "Net-(U2-C2CK{slash}~{RST})") (class "Default")
      (node (ref "P1") (pin "3") (pinfunction "3_3") (pintype "passive"))
      (node (ref "U2") (pin "8") (pinfunction "C2CK/~{RST}_8") (pintype "passive"))
    )
    (net (code "58") (name "Net-(U3A-IN+)") (class "Default")
      (node (ref "C10") (pin "1") (pinfunction "1_1") (pintype "passive"))
      (node (ref "R14") (pin "2") (pinfunction "2_2") (pintype "passive"))
      (node (ref "R15") (pin "1") (pinfunction "1_1") (pintype "passive"))
      (node (ref "U3") (pin "3") (pinfunction "IN+_3") (pintype "input"))
    )
    (net (code "59") (name "Net-(U3A-IN-)") (class "Default")
      (node (ref "R10") (pin "2") (pinfunction "2_2") (pintype "passive"))
      (node (ref "R7") (pin "1") (pinfunction "1_1") (pintype "passive"))
      (node (ref "U3") (pin "2") (pinfunction "IN-_2") (pintype "input"))
    )
    (net (code "60") (name "Net-(U3A-OUT)") (class "Default")
      (node (ref "R3") (pin "1") (pinfunction "1_1") (pintype "passive"))
      (node (ref "R7") (pin "2") (pinfunction "2_2") (pintype "passive"))
      (node (ref "U3") (pin "1") (pinfunction "OUT_1") (pintype "output"))
    )
    (net (code "61") (name "Net-(U3B-IN+)") (class "Default")
      (node (ref "C9") (pin "1") (pinfunction "1_1") (pintype "passive"))
      (node (ref "R15") (pin "2") (pinfunction "2_2") (pintype "passive"))
      (node (ref "R16") (pin "2") (pinfunction "2_2") (pintype "passive"))
      (node (ref "U3") (pin "5") (pinfunction "IN+_5") (pintype "input"))
    )
    (net (code "62") (name "Net-(U3B-IN-)") (class "Default")
      (node (ref "R12") (pin "2") (pinfunction "2_2") (pintype "passive"))
      (node (ref "R2") (pin "1") (pinfunction "1_1") (pintype "passive"))
      (node (ref "U3") (pin "6") (pinfunction "IN-_6") (pintype "input"))
    )
    (net (code "63") (name "Net-(U3B-OUT)") (class "Default")
      (node (ref "R13") (pin "1") (pinfunction "1_1") (pintype "passive"))
      (node (ref "R2") (pin "2") (pinfunction "2_2") (pintype "passive"))
      (node (ref "U3") (pin "7") (pinfunction "OUT_7") (pintype "output"))
    )
    (net (code "64") (name "Net-(U4-BYP)") (class "Default")
      (node (ref "C3") (pin "1") (pinfunction "1_1") (pintype "passive"))
      (node (ref "U4") (pin "4") (pinfunction "BYP_4") (pintype "passive"))
    )
    (net (code "65") (name "Net-(U4-EN)") (class "Default")
      (node (ref "R26") (pin "2") (pinfunction "2_2") (pintype "passive"))
      (node (ref "U4") (pin "3") (pinfunction "EN_3") (pintype "passive"))
    )
    (net (code "66") (name "Net-(U5-A)") (class "Default")
      (node (ref "R5") (pin "2") (pinfunction "2_2") (pintype "passive"))
      (node (ref "U5") (pin "6") (pinfunction "A_6") (pintype "passive"))
    )
    (net (code "67") (name "Net-(U5-B)") (class "Default")
      (node (ref "R1") (pin "2") (pinfunction "2_2") (pintype "passive"))
      (node (ref "U5") (pin "7") (pinfunction "B_7") (pintype "passive"))
    )
    (net (code "68") (name "VDD_+5V") (class "Default")
      (node (ref "C11") (pin "2") (pinfunction "2_2") (pintype "passive"))
      (node (ref "C13") (pin "1") (pinfunction "1_1") (pintype "passive"))
      (node (ref "C2") (pin "1") (pinfunction "1_1") (pintype "passive"))
      (node (ref "L1") (pin "2") (pinfunction "2_2") (pintype "passive"))
      (node (ref "Q3") (pin "2") (pinfunction "S_2") (pintype "passive"))
      (node (ref "Q4") (pin "2") (pinfunction "S_2") (pintype "passive"))
      (node (ref "Q5") (pin "2") (pinfunction "S_2") (pintype "passive"))
      (node (ref "R20") (pin "1") (pinfunction "1_1") (pintype "passive"))
      (node (ref "R22") (pin "1") (pinfunction "1_1") (pintype "passive"))
      (node (ref "R26") (pin "1") (pinfunction "1_1") (pintype "passive"))
      (node (ref "R6") (pin "1") (pinfunction "1_1") (pintype "passive"))
      (node (ref "R9") (pin "2") (pinfunction "2_2") (pintype "passive"))
      (node (ref "U4") (pin "1") (pinfunction "Vin_1") (pintype "passive"))
      (node (ref "U5") (pin "8") (pinfunction "VCC_8") (pintype "passive"))
    )
    (net (code "69") (name "unconnected-(U1-ON{slash}OFF-Pad5)") (class "Default")
      (node (ref "U1") (pin "5") (pinfunction "ON/OFF_5") (pintype "passive+no_connect"))
    )
    (net (code "70") (name "unconnected-(U3A-VCC-Pad8)") (class "Default")
      (node (ref "U3") (pin "8") (pinfunction "VCC_8") (pintype "power_in+no_connect"))
    )
    (net (code "71") (name "unconnected-(U3A-VEE-Pad4)") (class "Default")
      (node (ref "U3") (pin "4") (pinfunction "VEE_4") (pintype "power_in+no_connect"))
    )
  )
)
